# Hung_Doan.net
KiCad netlist of a schematic drawn in Altium Designer
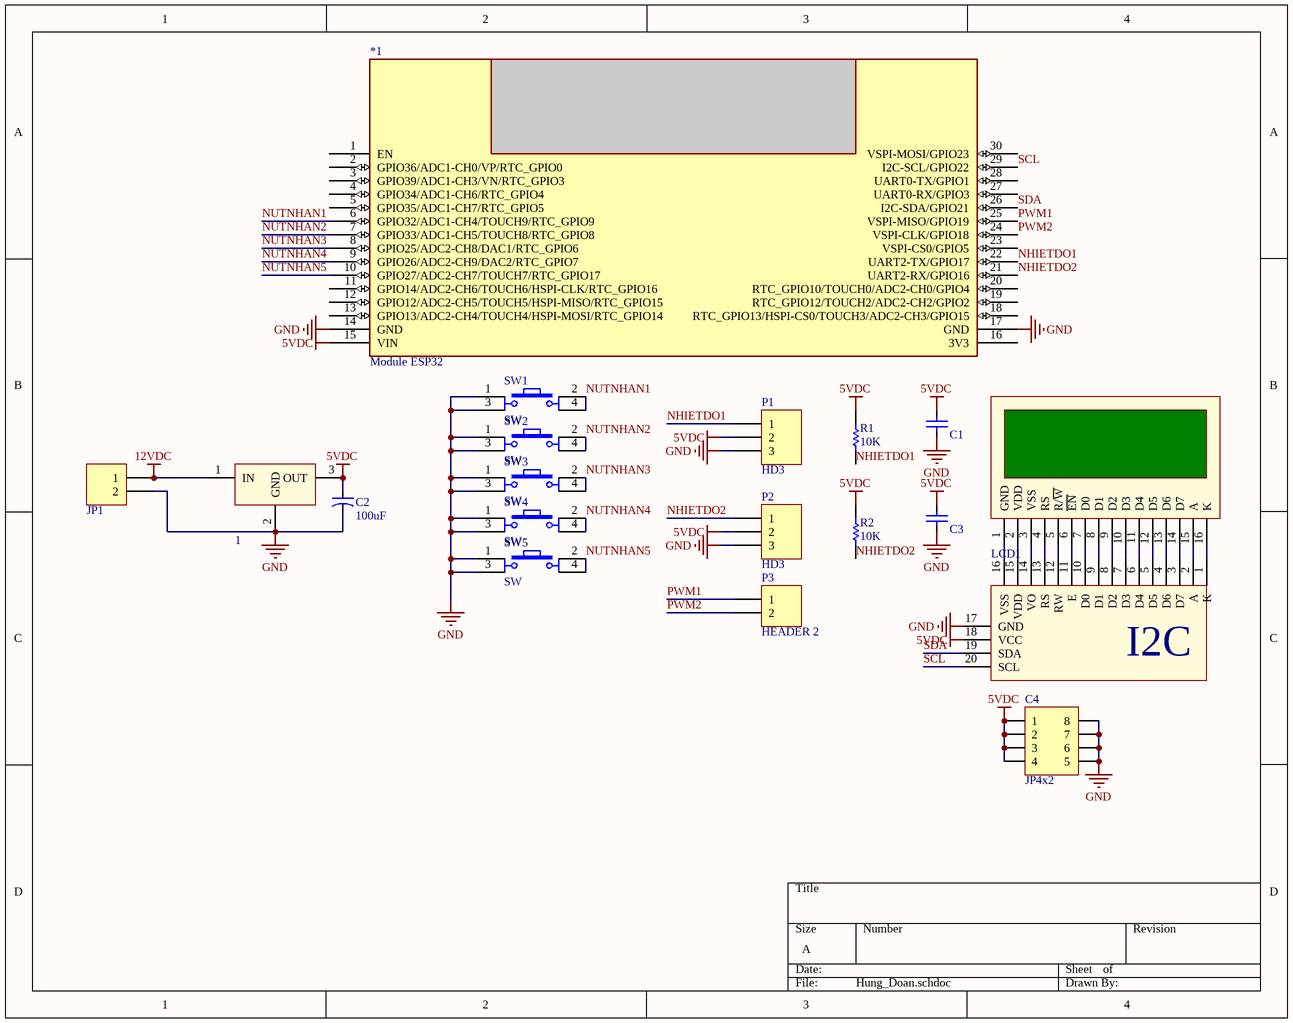
[diagram p0: Hung_Doan.schdoc]

(export (version "E")
  (design (tool "Eeschema 10.0.6"))
  (components
    (comp (ref "*1")
      (value "Module ESP32")
      (footprint "Module ESP32")
      (libsource (lib "Lib_NTD_HaUI") (part "Module ESP32"))
    )
    (comp (ref "*2")
      (value "Module I2C")
      (footprint "Module I2C")
      (libsource (lib "Lib_NTD_HaUI") (part "Module I2C"))
    )
    (comp (ref "1") (value "78Mxx") (footprint "TO252") (libsource (lib "Lib_NTD_HaUI") (part "78Mxx")))
    (comp (ref "C1")
      (value "104")
      (footprint "CAP-0805-SC")
      (libsource (lib "AltiumLibraryTieuBao") (part "CAP-SMDCHIP"))
    )
    (comp (ref "C2")
      (value "100uF")
      (footprint "CA-ALU-2.54")
      (description "Capacitor (Semiconductor SIM Model)")
      (fields (field (name "PUBLISHER") "Altium Limited"))
      (libsource (lib "LIBRARY") (part "CN-ALU-DIP"))
    )
    (comp (ref "C3")
      (value "104")
      (footprint "CAP-0805-SC")
      (libsource (lib "AltiumLibraryTieuBao") (part "CAP-SMDCHIP"))
    )
    (comp (ref "C4")
      (value "JP4x2")
      (footprint "JP4-D2C")
      (description "WR-PHD 2.54 mm Dual Socket Header")
      (fields
        (field (name "MANUFACTURER") "Würth Elektronik eiSos GmbH")
        (field (name "PARTNO") "61300821821")
        (field (name "CREATED BY") "Karrer Zheng")
      )
      (libsource (lib "LIBRARY") (part "JP4x2"))
    )
    (comp (ref "JP1")
      (value "Header 2_1")
      (footprint "HED2")
      (description "Header, 2-Pin")
      (fields (field (name "MANUFACTURER") "Generic Components"))
      (libsource (lib "syhaunguyen") (part "Header 2_1"))
    )
    (comp (ref "LCD1")
      (value "LCD 20x4")
      (footprint "LCD 20x4")
      (libsource (lib "Lib_NTD_HaUI") (part "LCD 20x4"))
    )
    (comp (ref "P1")
      (value "HD3")
      (footprint "XH 2.54-3P-CURVED")
      (libsource (lib "AltiumLibraryTieuBao") (part "HEADER 3"))
    )
    (comp (ref "P2")
      (value "HD3")
      (footprint "XH 2.54-3P-CURVED")
      (libsource (lib "AltiumLibraryTieuBao") (part "HEADER 3"))
    )
    (comp (ref "P3")
      (value "HEADER 2")
      (footprint "XH 2.54-2P-CURVED")
      (libsource (lib "AltiumLibraryTieuBao") (part "HEADER 2"))
    )
    (comp (ref "R1")
      (value "10K")
      (footprint "RES-0805-SC")
      (libsource (lib "AltiumLibraryTieuBao") (part "RES"))
    )
    (comp (ref "R2")
      (value "10K")
      (footprint "RES-0805-SC")
      (libsource (lib "AltiumLibraryTieuBao") (part "RES"))
    )
    (comp (ref "SW1")
      (value "SW")
      (footprint "SW4B")
      (description "Switch button 4 pin")
      (libsource (lib "syhaunguyen") (part "SW4"))
    )
    (comp (ref "SW2")
      (value "SW")
      (footprint "SW4B")
      (description "Switch button 4 pin")
      (libsource (lib "syhaunguyen") (part "SW4"))
    )
    (comp (ref "SW3")
      (value "SW")
      (footprint "SW4B")
      (description "Switch button 4 pin")
      (libsource (lib "syhaunguyen") (part "SW4"))
    )
    (comp (ref "SW4")
      (value "SW")
      (footprint "SW4B")
      (description "Switch button 4 pin")
      (libsource (lib "syhaunguyen") (part "SW4"))
    )
    (comp (ref "SW5")
      (value "SW")
      (footprint "SW4B")
      (description "Switch button 4 pin")
      (libsource (lib "syhaunguyen") (part "SW4"))
    )
  )
  (nets
    (net (code "1") (name "/NHIETDO1") (class "Default")
      (node (ref "*1") (pin "22") (pinfunction "UART2-TX/GPIO17_22") (pintype "bidirectional"))
      (node (ref "P1") (pin "1") (pinfunction "1_1") (pintype "passive"))
      (node (ref "R1") (pin "1") (pinfunction "1_1") (pintype "passive"))
    )
    (net (code "2") (name "/NHIETDO2") (class "Default")
      (node (ref "*1") (pin "21") (pinfunction "UART2-RX/GPIO16_21") (pintype "bidirectional"))
      (node (ref "P2") (pin "1") (pinfunction "1_1") (pintype "passive"))
      (node (ref "R2") (pin "1") (pinfunction "1_1") (pintype "passive"))
    )
    (net (code "3") (name "/NUTNHAN1") (class "Default")
      (node (ref "*1") (pin "6") (pinfunction "GPIO32/ADC1-CH4/TOUCH9/RTC_GPIO9_6") (pintype "bidirectional"))
      (node (ref "SW1") (pin "2") (pintype "passive"))
      (node (ref "SW1") (pin "4") (pintype "passive"))
    )
    (net (code "4") (name "/NUTNHAN2") (class "Default")
      (node (ref "*1") (pin "7") (pinfunction "GPIO33/ADC1-CH5/TOUCH8/RTC_GPIO8_7") (pintype "bidirectional"))
      (node (ref "SW2") (pin "2") (pintype "passive"))
      (node (ref "SW2") (pin "4") (pintype "passive"))
    )
    (net (code "5") (name "/NUTNHAN3") (class "Default")
      (node (ref "*1") (pin "8") (pinfunction "GPIO25/ADC2-CH8/DAC1/RTC_GPIO6_8") (pintype "bidirectional"))
      (node (ref "SW3") (pin "2") (pintype "passive"))
      (node (ref "SW3") (pin "4") (pintype "passive"))
    )
    (net (code "6") (name "/NUTNHAN4") (class "Default")
      (node (ref "*1") (pin "9") (pinfunction "GPIO26/ADC2-CH9/DAC2/RTC_GPIO7_9") (pintype "bidirectional"))
      (node (ref "SW4") (pin "2") (pintype "passive"))
      (node (ref "SW4") (pin "4") (pintype "passive"))
    )
    (net (code "7") (name "/NUTNHAN5") (class "Default")
      (node (ref "*1") (pin "10") (pinfunction "GPIO27/ADC2-CH7/TOUCH7/RTC_GPIO17_10") (pintype "bidirectional"))
      (node (ref "SW5") (pin "2") (pintype "passive"))
      (node (ref "SW5") (pin "4") (pintype "passive"))
    )
    (net (code "8") (name "/PWM1") (class "Default")
      (node (ref "*1") (pin "25") (pinfunction "VSPI-MISO/GPIO19_25") (pintype "bidirectional"))
      (node (ref "P3") (pin "1") (pinfunction "1_1") (pintype "passive"))
    )
    (net (code "9") (name "/PWM2") (class "Default")
      (node (ref "*1") (pin "24") (pinfunction "VSPI-CLK/GPIO18_24") (pintype "bidirectional"))
      (node (ref "P3") (pin "2") (pinfunction "2_2") (pintype "passive"))
    )
    (net (code "10") (name "/SCL") (class "Default")
      (node (ref "*1") (pin "29") (pinfunction "I2C-SCL/GPIO22_29") (pintype "bidirectional"))
      (node (ref "*2") (pin "20") (pinfunction "SCL_20") (pintype "passive"))
    )
    (net (code "11") (name "/SDA") (class "Default")
      (node (ref "*1") (pin "26") (pinfunction "I2C-SDA/GPIO21_26") (pintype "bidirectional"))
      (node (ref "*2") (pin "19") (pinfunction "SDA_19") (pintype "passive"))
    )
    (net (code "12") (name "5VDC") (class "Default")
      (node (ref "*1") (pin "15") (pinfunction "VIN_15") (pintype "power_in"))
      (node (ref "*2") (pin "18") (pinfunction "VCC_18") (pintype "passive"))
      (node (ref "1") (pin "3") (pinfunction "OUT_3") (pintype "passive"))
      (node (ref "C1") (pin "1") (pinfunction "1_1") (pintype "passive"))
      (node (ref "C2") (pin "1") (pinfunction "1_1") (pintype "passive"))
      (node (ref "C3") (pin "1") (pinfunction "1_1") (pintype "passive"))
      (node (ref "C4") (pin "1") (pinfunction "1_1") (pintype "passive"))
      (node (ref "C4") (pin "2") (pinfunction "2_2") (pintype "passive"))
      (node (ref "C4") (pin "3") (pinfunction "3_3") (pintype "passive"))
      (node (ref "C4") (pin "4") (pinfunction "4_4") (pintype "passive"))
      (node (ref "P1") (pin "2") (pinfunction "2_2") (pintype "passive"))
      (node (ref "P2") (pin "2") (pinfunction "2_2") (pintype "passive"))
      (node (ref "R1") (pin "2") (pinfunction "2_2") (pintype "passive"))
      (node (ref "R2") (pin "2") (pinfunction "2_2") (pintype "passive"))
    )
    (net (code "13") (name "12VDC") (class "Default")
      (node (ref "1") (pin "1") (pinfunction "IN_1") (pintype "passive"))
      (node (ref "JP1") (pin "1") (pinfunction "1_1") (pintype "passive"))
    )
    (net (code "14") (name "GND") (class "Default")
      (node (ref "*1") (pin "14") (pinfunction "GND_14") (pintype "power_in"))
      (node (ref "*1") (pin "17") (pinfunction "GND_17") (pintype "power_in"))
      (node (ref "*2") (pin "17") (pinfunction "GND_17") (pintype "passive"))
      (node (ref "1") (pin "2") (pinfunction "GND_2") (pintype "passive"))
      (node (ref "C1") (pin "2") (pinfunction "2_2") (pintype "passive"))
      (node (ref "C2") (pin "2") (pinfunction "2_2") (pintype "passive"))
      (node (ref "C3") (pin "2") (pinfunction "2_2") (pintype "passive"))
      (node (ref "C4") (pin "5") (pinfunction "5_5") (pintype "passive"))
      (node (ref "C4") (pin "6") (pinfunction "6_6") (pintype "passive"))
      (node (ref "C4") (pin "7") (pinfunction "7_7") (pintype "passive"))
      (node (ref "C4") (pin "8") (pinfunction "8_8") (pintype "passive"))
      (node (ref "JP1") (pin "2") (pinfunction "2_2") (pintype "passive"))
      (node (ref "P1") (pin "3") (pinfunction "3_3") (pintype "passive"))
      (node (ref "P2") (pin "3") (pinfunction "3_3") (pintype "passive"))
      (node (ref "SW1") (pin "1") (pintype "passive"))
      (node (ref "SW1") (pin "3") (pintype "passive"))
      (node (ref "SW2") (pin "1") (pintype "passive"))
      (node (ref "SW2") (pin "3") (pintype "passive"))
      (node (ref "SW3") (pin "1") (pintype "passive"))
      (node (ref "SW3") (pin "3") (pintype "passive"))
      (node (ref "SW4") (pin "1") (pintype "passive"))
      (node (ref "SW4") (pin "3") (pintype "passive"))
      (node (ref "SW5") (pin "1") (pintype "passive"))
      (node (ref "SW5") (pin "3") (pintype "passive"))
    )
    (net (code "15") (name "Net-(*2-A)") (class "Default")
      (node (ref "*2") (pin "2") (pinfunction "A_2") (pintype "passive"))
      (node (ref "LCD1") (pin "15") (pinfunction "A_15") (pintype "passive"))
    )
    (net (code "16") (name "Net-(*2-D0)") (class "Default")
      (node (ref "*2") (pin "10") (pinfunction "D0_10") (pintype "passive"))
      (node (ref "LCD1") (pin "7") (pinfunction "D0_7") (pintype "passive"))
    )
    (net (code "17") (name "Net-(*2-D1)") (class "Default")
      (node (ref "*2") (pin "9") (pinfunction "D1_9") (pintype "passive"))
      (node (ref "LCD1") (pin "8") (pinfunction "D1_8") (pintype "passive"))
    )
    (net (code "18") (name "Net-(*2-D2)") (class "Default")
      (node (ref "*2") (pin "8") (pinfunction "D2_8") (pintype "passive"))
      (node (ref "LCD1") (pin "9") (pinfunction "D2_9") (pintype "passive"))
    )
    (net (code "19") (name "Net-(*2-D3)") (class "Default")
      (node (ref "*2") (pin "7") (pinfunction "D3_7") (pintype "passive"))
      (node (ref "LCD1") (pin "10") (pinfunction "D3_10") (pintype "passive"))
    )
    (net (code "20") (name "Net-(*2-D4)") (class "Default")
      (node (ref "*2") (pin "6") (pinfunction "D4_6") (pintype "passive"))
      (node (ref "LCD1") (pin "11") (pinfunction "D4_11") (pintype "passive"))
    )
    (net (code "21") (name "Net-(*2-D5)") (class "Default")
      (node (ref "*2") (pin "5") (pinfunction "D5_5") (pintype "passive"))
      (node (ref "LCD1") (pin "12") (pinfunction "D5_12") (pintype "passive"))
    )
    (net (code "22") (name "Net-(*2-D6)") (class "Default")
      (node (ref "*2") (pin "4") (pinfunction "D6_4") (pintype "passive"))
      (node (ref "LCD1") (pin "13") (pinfunction "D6_13") (pintype "passive"))
    )
    (net (code "23") (name "Net-(*2-D7)") (class "Default")
      (node (ref "*2") (pin "3") (pinfunction "D7_3") (pintype "passive"))
      (node (ref "LCD1") (pin "14") (pinfunction "D7_14") (pintype "passive"))
    )
    (net (code "24") (name "Net-(*2-E)") (class "Default")
      (node (ref "*2") (pin "11") (pinfunction "E_11") (pintype "passive"))
      (node (ref "LCD1") (pin "6") (pinfunction "~{EN}_6") (pintype "passive"))
    )
    (net (code "25") (name "Net-(*2-K)") (class "Default")
      (node (ref "*2") (pin "1") (pinfunction "K_1") (pintype "passive"))
      (node (ref "LCD1") (pin "16") (pinfunction "K_16") (pintype "passive"))
    )
    (net (code "26") (name "Net-(*2-RS)") (class "Default")
      (node (ref "*2") (pin "13") (pinfunction "RS_13") (pintype "passive"))
      (node (ref "LCD1") (pin "4") (pinfunction "RS_4") (pintype "passive"))
    )
    (net (code "27") (name "Net-(*2-RW)") (class "Default")
      (node (ref "*2") (pin "12") (pinfunction "RW_12") (pintype "passive"))
      (node (ref "LCD1") (pin "5") (pinfunction "R/~{W}_5") (pintype "passive"))
    )
    (net (code "28") (name "Net-(*2-VDD)") (class "Default")
      (node (ref "*2") (pin "15") (pinfunction "VDD_15") (pintype "passive"))
      (node (ref "LCD1") (pin "2") (pinfunction "VDD_2") (pintype "passive"))
    )
    (net (code "29") (name "Net-(*2-VO)") (class "Default")
      (node (ref "*2") (pin "14") (pinfunction "VO_14") (pintype "passive"))
      (node (ref "LCD1") (pin "3") (pinfunction "VSS_3") (pintype "passive"))
    )
    (net (code "30") (name "Net-(*2-VSS)") (class "Default")
      (node (ref "*2") (pin "16") (pinfunction "VSS_16") (pintype "passive"))
      (node (ref "LCD1") (pin "1") (pinfunction "GND_1") (pintype "passive"))
    )
    (net (code "31") (name "unconnected-(*1-3V3-Pad16)") (class "Default")
      (node (ref "*1") (pin "16") (pinfunction "3V3_16") (pintype "power_in"))
    )
    (net (code "32") (name "unconnected-(*1-EN-Pad1)") (class "Default")
      (node (ref "*1") (pin "1") (pinfunction "EN_1") (pintype "passive"))
    )
    (net (code "33") (name "unconnected-(*1-GPIO12{slash}ADC2-CH5{slash}TOUCH5{slash}HSPI-MISO{slash}RTC_GPIO15-Pad12)") (class "Default")
      (node (ref "*1") (pin "12") (pinfunction "GPIO12/ADC2-CH5/TOUCH5/HSPI-MISO/RTC_GPIO15_12") (pintype "bidirectional"))
    )
    (net (code "34") (name "unconnected-(*1-GPIO13{slash}ADC2-CH4{slash}TOUCH4{slash}HSPI-MOSI{slash}RTC_GPIO14-Pad13)") (class "Default")
      (node (ref "*1") (pin "13") (pinfunction "GPIO13/ADC2-CH4/TOUCH4/HSPI-MOSI/RTC_GPIO14_13") (pintype "bidirectional"))
    )
    (net (code "35") (name "unconnected-(*1-GPIO14{slash}ADC2-CH6{slash}TOUCH6{slash}HSPI-CLK{slash}RTC_GPIO16-Pad11)") (class "Default")
      (node (ref "*1") (pin "11") (pinfunction "GPIO14/ADC2-CH6/TOUCH6/HSPI-CLK/RTC_GPIO16_11") (pintype "bidirectional"))
    )
    (net (code "36") (name "unconnected-(*1-GPIO34{slash}ADC1-CH6{slash}RTC_GPIO4-Pad4)") (class "Default")
      (node (ref "*1") (pin "4") (pinfunction "GPIO34/ADC1-CH6/RTC_GPIO4_4") (pintype "bidirectional"))
    )
    (net (code "37") (name "unconnected-(*1-GPIO35{slash}ADC1-CH7{slash}RTC_GPIO5-Pad5)") (class "Default")
      (node (ref "*1") (pin "5") (pinfunction "GPIO35/ADC1-CH7/RTC_GPIO5_5") (pintype "bidirectional"))
    )
    (net (code "38") (name "unconnected-(*1-GPIO36{slash}ADC1-CH0{slash}VP{slash}RTC_GPIO0-Pad2)") (class "Default")
      (node (ref "*1") (pin "2") (pinfunction "GPIO36/ADC1-CH0/VP/RTC_GPIO0_2") (pintype "bidirectional"))
    )
    (net (code "39") (name "unconnected-(*1-GPIO39{slash}ADC1-CH3{slash}VN{slash}RTC_GPIO3-Pad3)") (class "Default")
      (node (ref "*1") (pin "3") (pinfunction "GPIO39/ADC1-CH3/VN/RTC_GPIO3_3") (pintype "bidirectional"))
    )
    (net (code "40") (name "unconnected-(*1-RTC_GPIO10{slash}TOUCH0{slash}ADC2-CH0{slash}GPIO4-Pad20)") (class "Default")
      (node (ref "*1") (pin "20") (pinfunction "RTC_GPIO10/TOUCH0/ADC2-CH0/GPIO4_20") (pintype "bidirectional"))
    )
    (net (code "41") (name "unconnected-(*1-RTC_GPIO12{slash}TOUCH2{slash}ADC2-CH2{slash}GPIO2-Pad19)") (class "Default")
      (node (ref "*1") (pin "19") (pinfunction "RTC_GPIO12/TOUCH2/ADC2-CH2/GPIO2_19") (pintype "bidirectional"))
    )
    (net (code "42") (name "unconnected-(*1-RTC_GPIO13{slash}HSPI-CS0{slash}TOUCH3{slash}ADC2-CH3{slash}GPIO15-Pad18)") (class "Default")
      (node (ref "*1") (pin "18") (pinfunction "RTC_GPIO13/HSPI-CS0/TOUCH3/ADC2-CH3/GPIO15_18") (pintype "bidirectional"))
    )
    (net (code "43") (name "unconnected-(*1-UART0-RX{slash}GPIO3-Pad27)") (class "Default")
      (node (ref "*1") (pin "27") (pinfunction "UART0-RX/GPIO3_27") (pintype "bidirectional"))
    )
    (net (code "44") (name "unconnected-(*1-UART0-TX{slash}GPIO1-Pad28)") (class "Default")
      (node (ref "*1") (pin "28") (pinfunction "UART0-TX/GPIO1_28") (pintype "bidirectional"))
    )
    (net (code "45") (name "unconnected-(*1-VSPI-CS0{slash}GPIO5-Pad23)") (class "Default")
      (node (ref "*1") (pin "23") (pinfunction "VSPI-CS0/GPIO5_23") (pintype "bidirectional"))
    )
    (net (code "46") (name "unconnected-(*1-VSPI-MOSI{slash}GPIO23-Pad30)") (class "Default")
      (node (ref "*1") (pin "30") (pinfunction "VSPI-MOSI/GPIO23_30") (pintype "bidirectional"))
    )
  )
)
